# Phase_4.net
KiCad netlist of a schematic drawn in Altium Designer
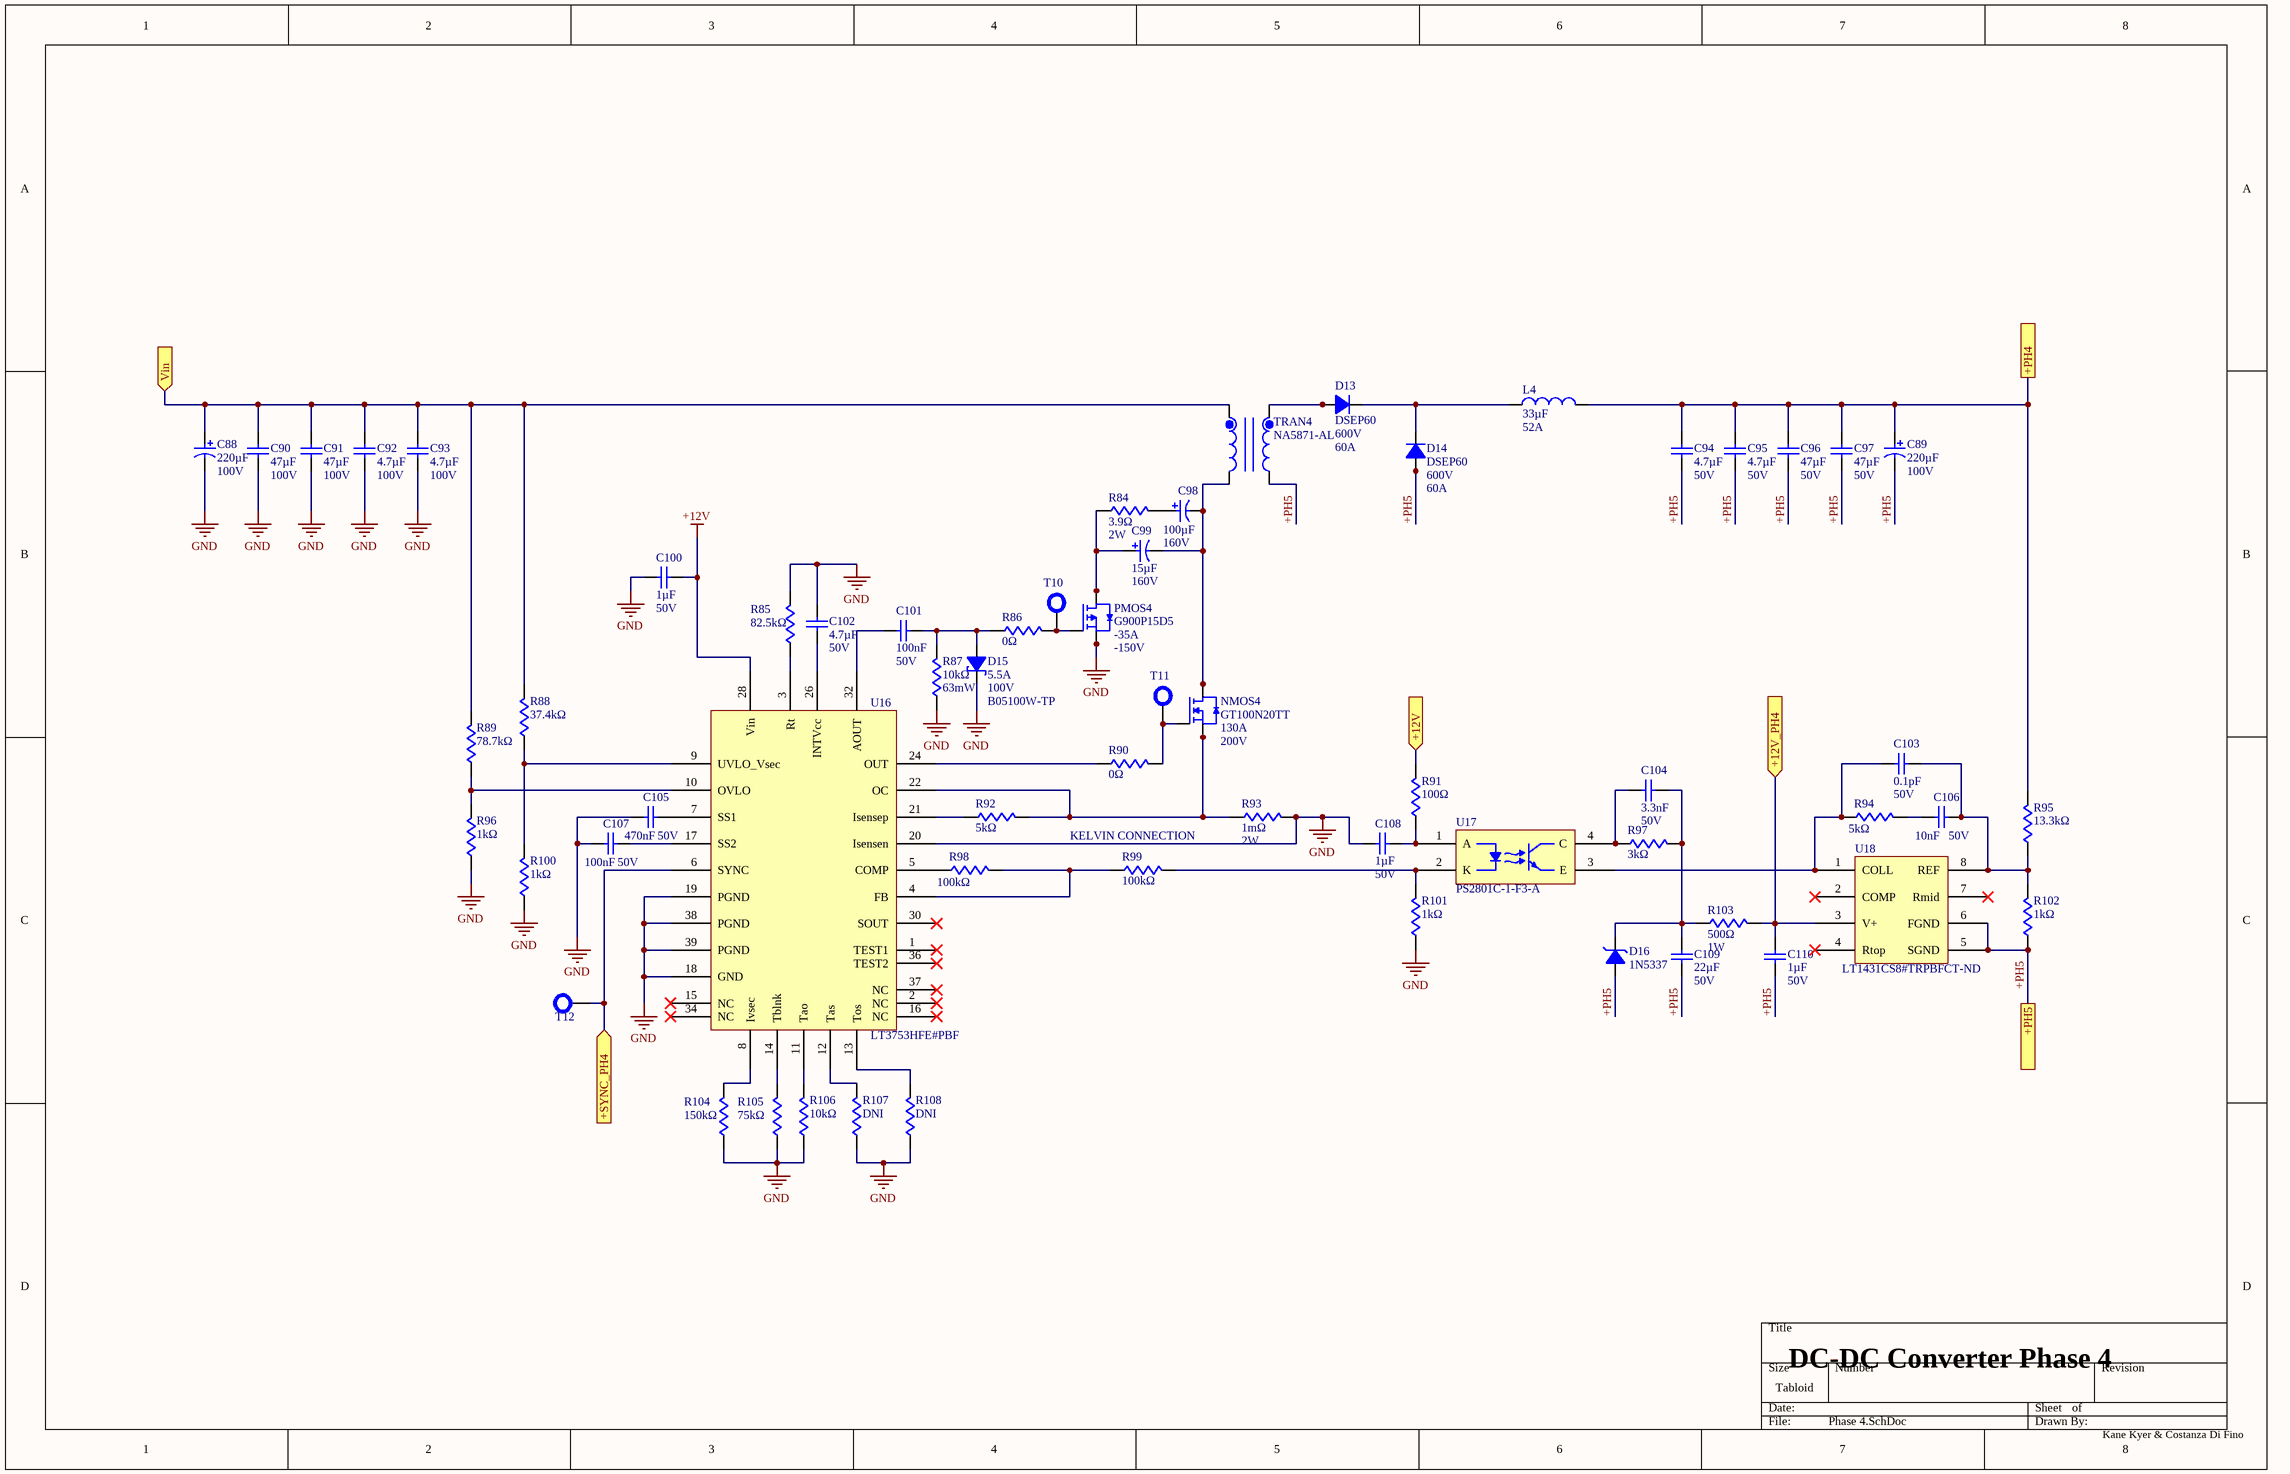
[diagram p0: Phase 4.SchDoc]

(export (version "E")
  (design (tool "Eeschema 10.0.6"))
  (components
    (comp (ref "C88")
      (value "220µF")
      (footprint "C_AEC")
      (description "Radial Can - SMD ALUMINUM ELECTROLYTIC CAPACITOR AFK 100V 220muF ±20% 0.709Dia 18.00mm")
      (fields
        (field (name "MANUFACTURER") "Cornell Dubilier")
        (field (name "MANUFACTURER PART NUMBER") "AFK227M2AR44T-F")
        (field (name "VOLTAGE RATING") "100V")
      )
      (libsource (lib "library") (part "AFK227M2AR44T-F"))
    )
    (comp (ref "C89")
      (value "220µF")
      (footprint "C_AEC")
      (description "Radial Can - SMD ALUMINUM ELECTROLYTIC CAPACITOR AFK 100V 220muF ±20% 0.709Dia 18.00mm")
      (fields
        (field (name "MANUFACTURER") "Cornell Dubilier")
        (field (name "MANUFACTURER PART NUMBER") "AFK227M2AR44T-F")
        (field (name "VOLTAGE RATING") "100V")
      )
      (libsource (lib "library") (part "AFK227M2AR44T-F"))
    )
    (comp (ref "C90")
      (value "47µF")
      (footprint "C_CAA573")
      (description "Multilayer Ceramic Chip Capacitors, Capacitance=47μF, LxWxT: 6.0x7.5x6.4mm")
      (fields
        (field (name "MANUFACTURER") "TDK")
        (field (name "MANUFACTURER PART NUMBER") "CAA573X7S2A476M640LH")
        (field (name "VOLTAGE RATING") "100V")
      )
      (libsource (lib "library") (part "CAA573X7S2A476M640LH"))
    )
    (comp (ref "C91")
      (value "47µF")
      (footprint "C_CAA573")
      (description "Multilayer Ceramic Chip Capacitors, Capacitance=47μF, LxWxT: 6.0x7.5x6.4mm")
      (fields
        (field (name "MANUFACTURER") "TDK")
        (field (name "MANUFACTURER PART NUMBER") "CAA573X7S2A476M640LH")
        (field (name "VOLTAGE RATING") "100V")
      )
      (libsource (lib "library") (part "CAA573X7S2A476M640LH"))
    )
    (comp (ref "C92")
      (value "4.7µF")
      (footprint "C_1210")
      (fields
        (field (name "MANUFACTURER") "Cal-Chip Electronics")
        (field (name "MANUFACTURER PART NUMBER") "GMC32X7S475K100NT")
        (field (name "VOLTAGE RATING (DC)") "100V")
      )
      (libsource (lib "library") (part "GMC32X7S475K100NT"))
    )
    (comp (ref "C93")
      (value "4.7µF")
      (footprint "C_1210")
      (fields
        (field (name "MANUFACTURER") "Cal-Chip Electronics")
        (field (name "MANUFACTURER PART NUMBER") "GMC32X7S475K100NT")
        (field (name "VOLTAGE RATING (DC)") "100V")
      )
      (libsource (lib "library") (part "GMC32X7S475K100NT"))
    )
    (comp (ref "C94")
      (value "4.7µF")
      (footprint "C_1206")
      (fields
        (field (name "MANUFACTURER") "Cal-Chip Electronics")
        (field (name "MANUFACTURER PART NUMBER") "GMC31X7R475K50NT")
        (field (name "VOLTAGE RATING (DC)") "50V")
      )
      (libsource (lib "library") (part "GMC31X7R475K50NT"))
    )
    (comp (ref "C95")
      (value "4.7µF")
      (footprint "C_1206")
      (fields
        (field (name "MANUFACTURER") "Cal-Chip Electronics")
        (field (name "MANUFACTURER PART NUMBER") "GMC31X7R475K50NT")
        (field (name "VOLTAGE RATING (DC)") "50V")
      )
      (libsource (lib "library") (part "GMC31X7R475K50NT"))
    )
    (comp (ref "C96")
      (value "47µF")
      (footprint "C_CKG57N")
      (fields
        (field (name "MANUFACTURER") "TDK")
        (field (name "MANUFACTURER PART NUMBER") "CKG57NX7R1H476M500JJ")
        (field (name "VOLTAGE RATING (DC)") "50V")
      )
      (libsource (lib "library") (part "CKG57NX7R1H476M500JJ"))
    )
    (comp (ref "C97")
      (value "47µF")
      (footprint "C_CKG57N")
      (fields
        (field (name "MANUFACTURER") "TDK")
        (field (name "MANUFACTURER PART NUMBER") "CKG57NX7R1H476M500JJ")
        (field (name "VOLTAGE RATING (DC)") "50V")
      )
      (libsource (lib "library") (part "CKG57NX7R1H476M500JJ"))
    )
    (comp (ref "C98")
      (value "100µF")
      (footprint "UUJ2C101MNJ1MS")
      (description "Aluminum Electrolytic Capacitors 100 F 160 V Radial, SMD 5000 Hrs 105C")
      (fields
        (field (name "MANUFACTURER") "Nichicon")
        (field (name "MANUFACTURER PART NUMBER") "UUJ2C101MNJ1MS")
        (field (name "VOLTAGE RATING (DC)") "160V")
      )
      (libsource (lib "library") (part "UUJ2C101MNJ1MS"))
    )
    (comp (ref "C99")
      (value "15µF")
      (footprint "ULT2C150MNL1GS")
      (description "Radial Can - SMD ALUMINUM ELECTROLYTIC CAPACITOR ULT 160V 15muF ±20% 0.315Dia 8.00mm")
      (fields
        (field (name "MANUFACTURER") "Nichicon")
        (field (name "MANUFACTURER PART NUMBER") "ULT2C150MNL1GS")
        (field (name "VOLTAGE") "160V")
      )
      (libsource (lib "library") (part "ULT2C150MNL1GS"))
    )
    (comp (ref "C100")
      (value "1µF")
      (footprint "C_0805")
      (description "50V 1uF X7R ±10% 0805 Multilayer Ceramic Capacitors MLCC - SMD/SMT ROHS")
      (fields
        (field (name "MANUFACTURER") "Samsung Electro-Mechanics")
        (field (name "MANUFACTURER PART NUMBER") "CL21B105KBFNNNE")
        (field (name "VOLTAGE") "50V")
      )
      (libsource (lib "library") (part "CL21B105KBFNNNE"))
    )
    (comp (ref "C101")
      (value "100nF")
      (footprint "C_0603")
      (description "50V 100nF X7R ±10% 0603 Multilayer Ceramic Capacitors MLCC - SMD/SMT ROHS")
      (fields
        (field (name "MANUFACTURER") "KEMET")
        (field (name "MANUFACTURER PART NUMBER") "C0603C104K5RACTU")
        (field (name "VOLTAGE RATING") "50V")
      )
      (libsource (lib "library") (part "C0603C104K5RACTU"))
    )
    (comp (ref "C102")
      (value "4.7µF")
      (footprint "C_1206")
      (fields
        (field (name "MANUFACTURER") "Cal-Chip Electronics")
        (field (name "MANUFACTURER PART NUMBER") "GMC31X7R475K50NT")
        (field (name "VOLTAGE RATING (DC)") "50V")
      )
      (libsource (lib "library") (part "GMC31X7R475K50NT"))
    )
    (comp (ref "C103")
      (value "0.1pF")
      (footprint "C_0402")
      (description "Multilayer Ceramic Capacitor, 0.1 pF, 50 V, ± 0.05pF, C0G (NP0), 0402 [1005 Metric]")
      (fields
        (field (name "MANUFACTURER") "Murata")
        (field (name "MANUFACTURER PART NUMBER") "GJM1555C1HR10WB01D")
        (field (name "VOLTAGE RATING") "50V")
      )
      (libsource (lib "library") (part "GJM1555C1HR10WB01D"))
    )
    (comp (ref "C104")
      (value "3.3nF")
      (footprint "C_0603")
      (description "50V 3.3nF C0G ±1% 0603 Multilayer Ceramic Capacitors MLCC - SMD/SMT ROHS")
      (fields
        (field (name "MANUFACTURER") "Murata")
        (field (name "MANUFACTURER PART NUMBER") "GCM1885C1H332FA16D")
        (field (name "VOLTAGE RATING") "50V")
      )
      (libsource (lib "library") (part "GCM1885C1H332FA16D"))
    )
    (comp (ref "C105")
      (value "470nF")
      (footprint "C_0402")
      (description "50V 470nF X5R ±10% 0402 Multilayer Ceramic Capacitors MLCC - SMD/SMT ROHS")
      (fields
        (field (name "MANUFACTURER") "Murata")
        (field (name "MANUFACTURER PART NUMBER") "GRM155R61H474KE11D")
        (field (name "VOLTAGE RATING") "50V")
      )
      (libsource (lib "library") (part "GRM155R61H474KE11D"))
    )
    (comp (ref "C106")
      (value "10nF")
      (footprint "C_0603")
      (description "Capacitor, Multilayer, Ceramic, 50V, 10%, X7R, 15% Tc, 0.01Uf, Surface Mount, 0603")
      (fields
        (field (name "MANUFACTURER") "KEMET")
        (field (name "MANUFACTURER PART NUMBER") "C0603C103K5RACTU")
        (field (name "VOLTAGE RATING") "50V")
      )
      (libsource (lib "library") (part "C0603C103K5RACTU"))
    )
    (comp (ref "C107")
      (value "100nF")
      (footprint "C_0603")
      (description "50V 100nF X7R ±10% 0603 Multilayer Ceramic Capacitors MLCC - SMD/SMT ROHS")
      (fields
        (field (name "MANUFACTURER") "KEMET")
        (field (name "MANUFACTURER PART NUMBER") "C0603C104K5RACTU")
        (field (name "VOLTAGE RATING") "50V")
      )
      (libsource (lib "library") (part "C0603C104K5RACTU"))
    )
    (comp (ref "C108")
      (value "1µF")
      (footprint "C_0805")
      (description "50V 1uF X7R ±10% 0805 Multilayer Ceramic Capacitors MLCC - SMD/SMT ROHS")
      (fields
        (field (name "MANUFACTURER") "Samsung Electro-Mechanics")
        (field (name "MANUFACTURER PART NUMBER") "CL21B105KBFNNNE")
        (field (name "VOLTAGE") "50V")
      )
      (libsource (lib "library") (part "CL21B105KBFNNNE"))
    )
    (comp (ref "C109")
      (value "22µF")
      (footprint "C_2220")
      (fields
        (field (name "MANUFACTURER") "Cal-Chip Electronics")
        (field (name "MANUFACTURER PART NUMBER") "GMC55X7R226M50NT")
        (field (name "VOLTAGE RATING (DC)") "50V")
      )
      (libsource (lib "library") (part "GMC55X7R226M50NT"))
    )
    (comp (ref "C110")
      (value "1µF")
      (footprint "C_0805")
      (description "50V 1uF X7R ±10% 0805 Multilayer Ceramic Capacitors MLCC - SMD/SMT ROHS")
      (fields
        (field (name "MANUFACTURER") "Samsung Electro-Mechanics")
        (field (name "MANUFACTURER PART NUMBER") "CL21B105KBFNNNE")
        (field (name "VOLTAGE") "50V")
      )
      (libsource (lib "library") (part "CL21B105KBFNNNE"))
    )
    (comp (ref "D13")
      (value "DSEP60")
      (footprint "D_DSEP60")
      (description "Power Diode Discretes-FRED TO-")
      (fields
        (field (name "MANUFACTURER") "IXYS")
        (field (name "MANUFACTURER PART NUMBER") "DSEP60-06AZ-TRL")
        (field (name "VR") "600V")
        (field (name "IO") "60A")
      )
      (libsource (lib "library") (part "DSEP60-06AZ-TRL"))
    )
    (comp (ref "D14")
      (value "DSEP60")
      (footprint "D_DSEP60")
      (description "Power Diode Discretes-FRED TO-")
      (fields
        (field (name "MANUFACTURER") "IXYS")
        (field (name "MANUFACTURER PART NUMBER") "DSEP60-06AZ-TRL")
        (field (name "VR") "600V")
        (field (name "IO") "60A")
      )
      (libsource (lib "library") (part "DSEP60-06AZ-TRL"))
    )
    (comp (ref "D15")
      (value "B05100W-TP")
      (footprint "D_B05100W")
      (description "Rectifier Diode, Schottky, 1 Phase, 1 Element, 0.5A, 100V V(RRM), Silicon")
      (fields
        (field (name "MANUFACTURER") "MCC")
        (field (name "MAX FORWARD SURGE CURRENT (IFSM)") "5.5A")
        (field (name "MIN BREAKDOWN VOLTAGE") "100V")
        (field (name "MANUFACTURER PART NUMBER") "B05100W-TP")
      )
      (libsource (lib "library") (part "B05100W-TP"))
    )
    (comp (ref "D16")
      (value "1N5337BRLG")
      (footprint "D_1N5337")
      (description "Zener Diode Single 4.7V 5% 2Ohm 5000mW 2-Pin Case 017AA-01 T/R / DIODE ZENER 4.7V 5W AXIAL")
      (fields
        (field (name "MANUFACTURER") "onsemi")
        (field (name "TOLERANCE") "5%")
        (field (name "SUPPLIER PART NUMBER") "1N5337")
      )
      (libsource (lib "library") (part "1N5337BRLG"))
    )
    (comp (ref "L4")
      (value "33µF")
      (footprint "CPEX4141L-330MC")
      (description "Fixed Ind 33UH 52A 1.88 Mohm Th")
      (fields
        (field (name "MANUFACTURER") "Codaca")
        (field (name "MANUFACTURER PART NUMBER") "CPEX4141L-330MC")
        (field (name "IRMS") "52A")
      )
      (libsource (lib "library") (part "CPEX4141L-330MC"))
    )
    (comp (ref "NMOS4")
      (value "GT100N20TT")
      (footprint "GT100N20TT")
      (description "Mosfet N-ch 200V 130A 280W Tolt")
      (fields
        (field (name "MANUFACTURER") "GoFord")
        (field (name "MANUFACTURER PART NUMBER") "GT100N20TT")
        (field (name "ID") "130A")
        (field (name "VDS") "200V")
      )
      (libsource (lib "library") (part "GT100N20TT"))
    )
    (comp (ref "PMOS4")
      (value "G900P15D5")
      (footprint "G900P15")
      (description "P-150V, -60A, RD(max) Less Than 80mOhm at -10V, VTH -1V to -4V, DFN5x6-8L")
      (fields
        (field (name "MANUFACTURER") "GoFord")
        (field (name "MANUFACTURER PART NUMBER") "G900P15D5")
        (field (name "ID") "-35A")
        (field (name "VDS") "-150V")
      )
      (libsource (lib "library") (part "G900P15D5"))
    )
    (comp (ref "R84")
      (value "3.9Ω")
      (footprint "R_SM2W")
      (description "SM Series 3.9 Ohm ±5 % 2 W ±200 ppm/°C Surface Mount Wirewound Resistor")
      (fields
        (field (name "MANUFACTURER") "TE Connectivity")
        (field (name "MANUFACTURER PART NUMBER") "SMW23R9JT")
        (field (name "POWER RATING") "2W")
      )
      (libsource (lib "library") (part "SMW23R9JT"))
    )
    (comp (ref "R85")
      (value "82.5kΩ")
      (footprint "R_0805")
      (description "Res Thick Film 0805 82.5K Ohm 1% 1/8W ±100ppm/°C Molded SMD SMD Paper T/R")
      (fields
        (field (name "MANUFACTURER") "Stackpole Electronics")
        (field (name "MANUFACTURER PART NUMBER") "RMCF0805FT82K5")
      )
      (libsource (lib "library") (part "RMCF0805FT82K5"))
    )
    (comp (ref "R86")
      (value "0Ω")
      (footprint "R_0805")
      (description "Zero Ohm Resistor, Jumper, 0805 [2012 Metric], Thick Film, 125 mW, 2.5 A, Surface Mount Device")
      (fields
        (field (name "MANUFACTURER") "Vishay")
        (field (name "MANUFACTURER PART NUMBER") "CRCW08050000Z0EA")
      )
      (libsource (lib "library") (part "CRCW08050000Z0EA"))
    )
    (comp (ref "R87")
      (value "10kΩ")
      (footprint "R_0402")
      (description "Fixed Resistor, Metal Glaze/thick Film, 0.0625W, 10000ohm, 50V, 1% +/-Tol, Surface Mount, 0402")
      (fields
        (field (name "MANUFACTURER") "Cal-Chip Electronics")
        (field (name "MANUFACTURER PART NUMBER") "RM04F1002CT")
        (field (name "POWER RATING") "63mW")
      )
      (libsource (lib "library") (part "RM04F1002CT"))
    )
    (comp (ref "R88")
      (value "37.4kΩ")
      (footprint "R_0603")
      (description "100mW Thick Film Resistors 75V ±100ppm/℃ ±1% 37.4kΩ 0603 Chip Resistor - Surface Mount ROHS")
      (fields
        (field (name "MANUFACTURER") "Yageo Group")
        (field (name "MANUFACTURER PART NUMBER") "RC0603FR-0737K4L")
      )
      (libsource (lib "library") (part "RC0603FR-0737K4L"))
    )
    (comp (ref "R89")
      (value "78.7kΩ")
      (footprint "R_0603")
      (description "Res Thick Film 0603 78.7K Ohm 1% 0.1W(1/10W) ±100ppm/C Pad SMD T/R")
      (fields
        (field (name "MANUFACTURER") "Yageo Group")
        (field (name "MANUFACTURER PART NUMBER") "RC0603FR-0778K7L")
      )
      (libsource (lib "library") (part "RC0603FR-0778K7L"))
    )
    (comp (ref "R90")
      (value "0Ω")
      (footprint "R_0805")
      (description "Zero Ohm Resistor, Jumper, 0805 [2012 Metric], Thick Film, 125 mW, 2.5 A, Surface Mount Device")
      (fields
        (field (name "MANUFACTURER") "Vishay")
        (field (name "MANUFACTURER PART NUMBER") "CRCW08050000Z0EA")
      )
      (libsource (lib "library") (part "CRCW08050000Z0EA"))
    )
    (comp (ref "R91")
      (value "100Ω")
      (footprint "R_0603")
      (description "Yageo RC0603FR-07100RL 0603 SMD Resistor 100 Ohm thin film chip resistor")
      (fields
        (field (name "MANUFACTURER") "Yageo Group")
        (field (name "MANUFACTURER PART NUMBER") "RC0603FR-07100RL")
      )
      (libsource (lib "library") (part "RC0603FR-07100RL"))
    )
    (comp (ref "R92")
      (value "5kΩ")
      (footprint "R_0402")
      (description "Res Thin Film 0402 5K Ohm 0.1% 0.05W(1/20W) +/-25ppm/C Sulfur Resistant Pad SMD Medical T/R")
      (fields
        (field (name "MANUFACTURER") "Vishay")
        (field (name "MANUFACTURER PART NUMBER") "PNM0402E5001BST1")
      )
      (libsource (lib "library") (part "PNM0402E5001BST1"))
    )
    (comp (ref "R93")
      (value "1mΩ")
      (footprint "R_2512")
      (description "Res Thick Film 2512 1m Ohm 1% 2W ±75ppm/°C Molded SMD Embossed T/R")
      (fields
        (field (name "MANUFACTURER") "Bourns")
        (field (name "MANUFACTURER PART NUMBER") "CRE2512-FZ-R001E-2")
        (field (name "POWER RATING") "2W")
      )
      (libsource (lib "library") (part "CRE2512-FZ-R001E-2"))
    )
    (comp (ref "R94")
      (value "5kΩ")
      (footprint "R_0402")
      (description "Res Thin Film 0402 5K Ohm 0.1% 0.05W(1/20W) +/-25ppm/C Sulfur Resistant Pad SMD Medical T/R")
      (fields
        (field (name "MANUFACTURER") "Vishay")
        (field (name "MANUFACTURER PART NUMBER") "PNM0402E5001BST1")
      )
      (libsource (lib "library") (part "PNM0402E5001BST1"))
    )
    (comp (ref "R95")
      (value "13.3kΩ")
      (footprint "R_0603")
      (description "Res Thick Film 0603 13.3K Ohm 1% 0.1W(1/10W) ±100ppm/C Pad SMD Automotive T/R")
      (fields
        (field (name "MANUFACTURER") "Stackpole Electronics")
        (field (name "MANUFACTURER PART NUMBER") "RMCF0603FT13K3")
      )
      (libsource (lib "library") (part "RMCF0603FT13K3"))
    )
    (comp (ref "R96")
      (value "1kΩ")
      (footprint "R_0402")
      (description "62.5mW Thick Film Resistors ±100ppm/℃ ±1% 1kΩ 0402 Chip Resistor - Surface Mount ROHS")
      (fields
        (field (name "MANUFACTURER") "Cal-Chip Electronics")
        (field (name "MANUFACTURER PART NUMBER") "RM04F1001CT")
      )
      (libsource (lib "library") (part "RM04F1001CT"))
    )
    (comp (ref "R97")
      (value "3kΩ")
      (footprint "C_0402")
      (description "Res Thick Film 0402 3K Ohm 1% 0.063W(1/16W) ±100ppm/C Pad SMD Automotive T/R")
      (fields
        (field (name "MANUFACTURER") "Yageo Group")
        (field (name "MANUFACTURER PART NUMBER") "AC0402FR-073KL")
      )
      (libsource (lib "library") (part "AC0402FR-073KL"))
    )
    (comp (ref "R98")
      (value "100kΩ")
      (footprint "R_0402")
      (description "Fixed Resistor, Metal Glaze/thick Film, 0.0625W, 100000ohm, 50V, 1% +/-Tol, Surface Mount, 0402")
      (fields
        (field (name "MANUFACTURER") "Cal-Chip Electronics")
        (field (name "MANUFACTURER PART NUMBER") "RM04F1003CT")
      )
      (libsource (lib "library") (part "RM04F1003CT"))
    )
    (comp (ref "R99")
      (value "100kΩ")
      (footprint "R_0402")
      (description "Fixed Resistor, Metal Glaze/thick Film, 0.0625W, 100000ohm, 50V, 1% +/-Tol, Surface Mount, 0402")
      (fields
        (field (name "MANUFACTURER") "Cal-Chip Electronics")
        (field (name "MANUFACTURER PART NUMBER") "RM04F1003CT")
      )
      (libsource (lib "library") (part "RM04F1003CT"))
    )
    (comp (ref "R100")
      (value "1kΩ")
      (footprint "R_0402")
      (description "62.5mW Thick Film Resistors ±100ppm/℃ ±1% 1kΩ 0402 Chip Resistor - Surface Mount ROHS")
      (fields
        (field (name "MANUFACTURER") "Cal-Chip Electronics")
        (field (name "MANUFACTURER PART NUMBER") "RM04F1001CT")
      )
      (libsource (lib "library") (part "RM04F1001CT"))
    )
    (comp (ref "R101")
      (value "1kΩ")
      (footprint "R_0402")
      (description "62.5mW Thick Film Resistors ±100ppm/℃ ±1% 1kΩ 0402 Chip Resistor - Surface Mount ROHS")
      (fields
        (field (name "MANUFACTURER") "Cal-Chip Electronics")
        (field (name "MANUFACTURER PART NUMBER") "RM04F1001CT")
      )
      (libsource (lib "library") (part "RM04F1001CT"))
    )
    (comp (ref "R102")
      (value "1kΩ")
      (footprint "R_0402")
      (description "62.5mW Thick Film Resistors ±100ppm/℃ ±1% 1kΩ 0402 Chip Resistor - Surface Mount ROHS")
      (fields
        (field (name "MANUFACTURER") "Cal-Chip Electronics")
        (field (name "MANUFACTURER PART NUMBER") "RM04F1001CT")
      )
      (libsource (lib "library") (part "RM04F1001CT"))
    )
    (comp (ref "R103")
      (value "500Ω")
      (footprint "R_WSC2515")
      (description "Fixed Resistor, Wire Wound, 1W, 500ohm, 22.3607V, 1% +/-Tol, 20ppm/Cel, Surface Mount, 2515")
      (fields
        (field (name "MANUFACTURER") "Vishay")
        (field (name "MANUFACTURER PART NUMBER") "WSC2515500R0FEB")
        (field (name "POWER RATING") "1W")
      )
      (libsource (lib "library") (part "WSC2515500R0FEB"))
    )
    (comp (ref "R104")
      (value "150kΩ")
      (footprint "R_0603")
      (description "100mW Thick Film Resistors 75V ±100ppm/℃ ±1% 150kΩ 0603 Chip Resistor - Surface Mount ROHS")
      (fields
        (field (name "MANUFACTURER") "Yageo Group")
        (field (name "MANUFACTURER PART NUMBER") "RC0603FR-07150KL")
      )
      (libsource (lib "library") (part "RC0603FR-07150KL"))
    )
    (comp (ref "R105")
      (value "75kΩ")
      (footprint "R_0603")
      (description "Res Thick Film 0603 75K Ohm 1% 0.1W(1/10W) ±100ppm/C Pad SMD T/R Automotive AEC-Q200")
      (fields
        (field (name "MANUFACTURER") "Yageo Group")
        (field (name "MANUFACTURER PART NUMBER") "AC0603FR-0775KL")
      )
      (libsource (lib "library") (part "AC0603FR-0775KL"))
    )
    (comp (ref "R106")
      (value "10kΩ")
      (footprint "R_0402")
      (description "Fixed Resistor, Metal Glaze/thick Film, 0.0625W, 10000ohm, 50V, 1% +/-Tol, Surface Mount, 0402")
      (fields
        (field (name "MANUFACTURER") "Cal-Chip Electronics")
        (field (name "MANUFACTURER PART NUMBER") "RM04F1002CT")
      )
      (libsource (lib "library") (part "RM04F1002CT"))
    )
    (comp (ref "R107")
      (value "DNI")
      (footprint "R_0805")
      (description "Zero Ohm Resistor, Jumper, 0805 [2012 Metric], Thick Film, 125 mW, 2.5 A, Surface Mount Device")
      (fields
        (field (name "MANUFACTURER") "Vishay")
        (field (name "MANUFACTURER PART NUMBER") "CRCW08050000Z0EA")
      )
      (libsource (lib "library") (part "CRCW08050000Z0EA"))
    )
    (comp (ref "R108")
      (value "DNI")
      (footprint "R_0805")
      (description "Zero Ohm Resistor, Jumper, 0805 [2012 Metric], Thick Film, 125 mW, 2.5 A, Surface Mount Device")
      (fields
        (field (name "MANUFACTURER") "Vishay")
        (field (name "MANUFACTURER PART NUMBER") "CRCW08050000Z0EA")
      )
      (libsource (lib "library") (part "CRCW08050000Z0EA"))
    )
    (comp (ref "T10") (value "TEST") (footprint "TEST_POINT") (libsource (lib "library") (part "TEST")))
    (comp (ref "T11") (value "TEST") (footprint "TEST_POINT") (libsource (lib "library") (part "TEST")))
    (comp (ref "T12") (value "TEST") (footprint "TEST_POINT") (libsource (lib "library") (part "TEST")))
    (comp (ref "TRAN4")
      (value "NA5871-AL")
      (footprint "NA5871-AL")
      (description "Transformer, planar, for TI UCC28950, SMT, RoHS")
      (fields (field (name "MANUFACTURER") "Coilcraft") (field (name "SUPPLIER PART NUMBER") "NA5871-AL"))
      (libsource (lib "library") (part "NA5871-AL"))
    )
    (comp (ref "U16")
      (value "LT3753HFE#PBF")
      (footprint "LT3753")
      (description "500kHz 8.5V~100V Buck-boost type 1 TSSOP-38-EP-4.4mm DC-DC Controllers ROHS")
      (fields
        (field (name "MANUFACTURER") "Analog Devices")
        (field (name "MANUFACTURER PART NUMBER") "LT3753HFE#PBF")
      )
      (libsource (lib "library") (part "LT3753HFE#PBF"))
    )
    (comp (ref "U17")
      (value "PS2801C-1-F3-A")
      (footprint "PS2801C")
      (description "Optocoupler DC-IN 1-CH Transistor DC-OUT 4-Pin SSOP T/R")
      (fields
        (field (name "MANUFACTURER") "Renesas")
        (field (name "MANUFACTURER PART NUMBER") "PS2801C-1-F3-A")
      )
      (libsource (lib "library") (part "PS2801C-1-F3-A"))
    )
    (comp (ref "U18")
      (value "LT1431CS8#TRPBF")
      (footprint "LT1431")
      (description "V-Ref Adjustable 2.5V to 36V 100mA 8-Pin SOIC N T/R")
      (fields
        (field (name "SUPPLIER PART NUMBER") "LT1431CS8#TRPBFCT-ND")
        (field (name "MANUFACTURER") "Analog Devices")
        (field (name "TOLERANCE") "0.4%")
      )
      (libsource (lib "library") (part "LT1431CS8#TRPBF"))
    )
  )
  (nets
    (net (code "1") (name "+12V") (class "Default")
      (node (ref "C100") (pin "2") (pintype "passive"))
      (node (ref "R91") (pin "2") (pintype "passive"))
      (node (ref "U16") (pin "28") (pinfunction "Vin_28") (pintype "passive"))
    )
    (net (code "2") (name "/+12V_PH4") (class "Default")
      (node (ref "C110") (pin "2") (pintype "passive"))
      (node (ref "R103") (pin "2") (pintype "passive"))
      (node (ref "U18") (pin "3") (pinfunction "V+_3") (pintype "passive"))
    )
    (net (code "3") (name "/+PH4") (class "Default")
      (node (ref "C89") (pin "1") (pintype "passive"))
      (node (ref "C94") (pin "2") (pintype "passive"))
      (node (ref "C95") (pin "2") (pintype "passive"))
      (node (ref "C96") (pin "2") (pintype "passive"))
      (node (ref "C97") (pin "2") (pintype "passive"))
      (node (ref "L4") (pin "2") (pintype "passive"))
      (node (ref "R95") (pin "2") (pintype "passive"))
    )
    (net (code "4") (name "/+PH5") (class "Default")
      (node (ref "C109") (pin "1") (pintype "passive"))
      (node (ref "C110") (pin "1") (pintype "passive"))
      (node (ref "C89") (pin "2") (pintype "passive"))
      (node (ref "C94") (pin "1") (pintype "passive"))
      (node (ref "C95") (pin "1") (pintype "passive"))
      (node (ref "C96") (pin "1") (pintype "passive"))
      (node (ref "C97") (pin "1") (pintype "passive"))
      (node (ref "D14") (pin "1") (pinfunction "A_1") (pintype "passive"))
      (node (ref "D14") (pin "3") (pinfunction "A_3") (pintype "passive"))
      (node (ref "D16") (pin "2") (pintype "passive"))
      (node (ref "R102") (pin "1") (pintype "passive"))
      (node (ref "TRAN4") (pin "11") (pintype "passive"))
      (node (ref "U18") (pin "5") (pinfunction "SGND_5") (pintype "passive"))
      (node (ref "U18") (pin "6") (pinfunction "FGND_6") (pintype "passive"))
    )
    (net (code "5") (name "/+SYNC_PH4") (class "Default")
      (node (ref "T12") (pin "1") (pinfunction "1_1") (pintype "passive"))
      (node (ref "U16") (pin "6") (pinfunction "SYNC_6") (pintype "passive"))
    )
    (net (code "6") (name "/Vin") (class "Default")
      (node (ref "C88") (pin "1") (pintype "passive"))
      (node (ref "C90") (pin "2") (pintype "passive"))
      (node (ref "C91") (pin "2") (pintype "passive"))
      (node (ref "C92") (pin "2") (pintype "passive"))
      (node (ref "C93") (pin "2") (pintype "passive"))
      (node (ref "R88") (pin "2") (pintype "passive"))
      (node (ref "R89") (pin "2") (pintype "passive"))
      (node (ref "TRAN4") (pin "1") (pintype "passive"))
    )
    (net (code "7") (name "GND") (class "Default")
      (node (ref "C100") (pin "1") (pintype "passive"))
      (node (ref "C102") (pin "1") (pintype "passive"))
      (node (ref "C105") (pin "1") (pintype "passive"))
      (node (ref "C107") (pin "1") (pintype "passive"))
      (node (ref "C108") (pin "1") (pintype "passive"))
      (node (ref "C88") (pin "2") (pintype "passive"))
      (node (ref "C90") (pin "1") (pintype "passive"))
      (node (ref "C91") (pin "1") (pintype "passive"))
      (node (ref "C92") (pin "1") (pintype "passive"))
      (node (ref "C93") (pin "1") (pintype "passive"))
      (node (ref "D15") (pin "1") (pintype "passive"))
      (node (ref "PMOS4") (pin "1") (pinfunction "S_1") (pintype "passive"))
      (node (ref "PMOS4") (pin "2") (pinfunction "S_2") (pintype "passive"))
      (node (ref "PMOS4") (pin "3") (pinfunction "S_3") (pintype "passive"))
      (node (ref "R100") (pin "1") (pintype "passive"))
      (node (ref "R101") (pin "1") (pintype "passive"))
      (node (ref "R104") (pin "1") (pintype "passive"))
      (node (ref "R105") (pin "1") (pintype "passive"))
      (node (ref "R106") (pin "1") (pintype "passive"))
      (node (ref "R107") (pin "1") (pintype "passive"))
      (node (ref "R108") (pin "1") (pintype "passive"))
      (node (ref "R85") (pin "2") (pintype "passive"))
      (node (ref "R87") (pin "1") (pintype "passive"))
      (node (ref "R93") (pin "2") (pintype "passive"))
      (node (ref "R96") (pin "1") (pintype "passive"))
      (node (ref "U16") (pin "18") (pinfunction "GND_18") (pintype "passive"))
      (node (ref "U16") (pin "19") (pinfunction "PGND_19") (pintype "passive"))
      (node (ref "U16") (pin "20") (pinfunction "Isensen_20") (pintype "passive"))
      (node (ref "U16") (pin "38") (pinfunction "PGND_38") (pintype "passive"))
      (node (ref "U16") (pin "39") (pinfunction "PGND_39") (pintype "passive"))
    )
    (net (code "8") (name "Net-(C98-Pad1)") (class "Default")
      (node (ref "C98") (pin "1") (pintype "passive"))
      (node (ref "R84") (pin "2") (pintype "passive"))
    )
    (net (code "9") (name "Net-(C98-Pad2)") (class "Default")
      (node (ref "C98") (pin "2") (pintype "passive"))
      (node (ref "C99") (pin "2") (pintype "passive"))
      (node (ref "NMOS4") (pin "10") (pinfunction "D_10") (pintype "passive"))
      (node (ref "NMOS4") (pin "11") (pinfunction "D_11") (pintype "passive"))
      (node (ref "NMOS4") (pin "12") (pinfunction "D_12") (pintype "passive"))
      (node (ref "NMOS4") (pin "13") (pinfunction "D_13") (pintype "passive"))
      (node (ref "NMOS4") (pin "14") (pinfunction "D_14") (pintype "passive"))
      (node (ref "NMOS4") (pin "15") (pinfunction "D_15") (pintype "passive"))
      (node (ref "NMOS4") (pin "16") (pinfunction "D_16") (pintype "passive"))
      (node (ref "NMOS4") (pin "9") (pinfunction "D_9") (pintype "passive"))
      (node (ref "TRAN4") (pin "4") (pintype "passive"))
    )
    (net (code "10") (name "Net-(C99-Pad1)") (class "Default")
      (node (ref "C99") (pin "1") (pintype "passive"))
      (node (ref "PMOS4") (pin "5") (pinfunction "D_5") (pintype "passive"))
      (node (ref "PMOS4") (pin "6") (pinfunction "D_6") (pintype "passive"))
      (node (ref "PMOS4") (pin "7") (pinfunction "D_7") (pintype "passive"))
      (node (ref "PMOS4") (pin "8") (pinfunction "D_8") (pintype "passive"))
      (node (ref "R84") (pin "1") (pintype "passive"))
    )
    (net (code "11") (name "Net-(C101-Pad2)") (class "Default")
      (node (ref "C101") (pin "2") (pintype "passive"))
      (node (ref "D15") (pin "2") (pintype "passive"))
      (node (ref "R86") (pin "1") (pintype "passive"))
      (node (ref "R87") (pin "2") (pintype "passive"))
    )
    (net (code "12") (name "Net-(C104-Pad2)") (class "Default")
      (node (ref "C104") (pin "2") (pintype "passive"))
      (node (ref "C109") (pin "2") (pintype "passive"))
      (node (ref "D16") (pin "1") (pintype "passive"))
      (node (ref "R103") (pin "1") (pintype "passive"))
      (node (ref "R97") (pin "2") (pintype "passive"))
    )
    (net (code "13") (name "Net-(C106-Pad1)") (class "Default")
      (node (ref "C106") (pin "1") (pintype "passive"))
      (node (ref "R94") (pin "2") (pintype "passive"))
    )
    (net (code "14") (name "Net-(D13-A-Pad1)") (class "Default")
      (node (ref "D13") (pin "1") (pinfunction "A_1") (pintype "passive"))
      (node (ref "D13") (pin "3") (pinfunction "A_3") (pintype "passive"))
      (node (ref "TRAN4") (pin "6") (pintype "passive"))
    )
    (net (code "15") (name "Net-(D13-C)") (class "Default")
      (node (ref "D13") (pin "4") (pinfunction "C_4") (pintype "passive"))
      (node (ref "D14") (pin "4") (pinfunction "C_4") (pintype "passive"))
      (node (ref "L4") (pin "1") (pintype "passive"))
    )
    (net (code "16") (name "Net-(NMOS4-G)") (class "Default")
      (node (ref "NMOS4") (pin "8") (pinfunction "G_8") (pintype "passive"))
      (node (ref "R90") (pin "2") (pintype "passive"))
      (node (ref "T11") (pin "1") (pinfunction "1_1") (pintype "passive"))
    )
    (net (code "17") (name "Net-(PMOS4-G)") (class "Default")
      (node (ref "PMOS4") (pin "4") (pinfunction "G_4") (pintype "passive"))
      (node (ref "R86") (pin "2") (pintype "passive"))
      (node (ref "T10") (pin "1") (pinfunction "1_1") (pintype "passive"))
    )
    (net (code "18") (name "Net-(U16-AOUT)") (class "Default")
      (node (ref "C101") (pin "1") (pintype "passive"))
      (node (ref "U16") (pin "32") (pinfunction "AOUT_32") (pintype "passive"))
    )
    (net (code "19") (name "Net-(U16-COMP)") (class "Default")
      (node (ref "R98") (pin "1") (pintype "passive"))
      (node (ref "U16") (pin "5") (pinfunction "COMP_5") (pintype "passive"))
    )
    (net (code "20") (name "Net-(U16-FB)") (class "Default")
      (node (ref "R98") (pin "2") (pintype "passive"))
      (node (ref "R99") (pin "1") (pintype "passive"))
      (node (ref "U16") (pin "4") (pinfunction "FB_4") (pintype "passive"))
    )
    (net (code "21") (name "Net-(U16-INTVcc)") (class "Default")
      (node (ref "C102") (pin "2") (pintype "passive"))
      (node (ref "U16") (pin "26") (pinfunction "INTVcc_26") (pintype "passive"))
    )
    (net (code "22") (name "Net-(U16-Isensep)") (class "Default")
      (node (ref "R92") (pin "1") (pintype "passive"))
      (node (ref "U16") (pin "21") (pinfunction "Isensep_21") (pintype "passive"))
    )
    (net (code "23") (name "Net-(U16-Ivsec)") (class "Default")
      (node (ref "R104") (pin "2") (pintype "passive"))
      (node (ref "U16") (pin "8") (pinfunction "Ivsec_8") (pintype "passive"))
    )
    (net (code "24") (name "Net-(U16-OC)") (class "Default")
      (node (ref "NMOS4") (pin "1") (pinfunction "S_1") (pintype "passive"))
      (node (ref "NMOS4") (pin "2") (pinfunction "S_2") (pintype "passive"))
      (node (ref "NMOS4") (pin "3") (pinfunction "S_3") (pintype "passive"))
      (node (ref "NMOS4") (pin "4") (pinfunction "S_4") (pintype "passive"))
      (node (ref "NMOS4") (pin "5") (pinfunction "S_5") (pintype "passive"))
      (node (ref "NMOS4") (pin "6") (pinfunction "S_6") (pintype "passive"))
      (node (ref "NMOS4") (pin "7") (pinfunction "S_7") (pintype "passive"))
      (node (ref "R92") (pin "2") (pintype "passive"))
      (node (ref "R93") (pin "1") (pintype "passive"))
      (node (ref "U16") (pin "22") (pinfunction "OC_22") (pintype "passive"))
    )
    (net (code "25") (name "Net-(U16-OUT)") (class "Default")
      (node (ref "R90") (pin "1") (pintype "passive"))
      (node (ref "U16") (pin "24") (pinfunction "OUT_24") (pintype "passive"))
    )
    (net (code "26") (name "Net-(U16-OVLO)") (class "Default")
      (node (ref "R89") (pin "1") (pintype "passive"))
      (node (ref "R96") (pin "2") (pintype "passive"))
      (node (ref "U16") (pin "10") (pinfunction "OVLO_10") (pintype "passive"))
    )
    (net (code "27") (name "Net-(U16-Rt)") (class "Default")
      (node (ref "R85") (pin "1") (pintype "passive"))
      (node (ref "U16") (pin "3") (pinfunction "Rt_3") (pintype "passive"))
    )
    (net (code "28") (name "Net-(U16-SS1)") (class "Default")
      (node (ref "C105") (pin "2") (pintype "passive"))
      (node (ref "U16") (pin "7") (pinfunction "SS1_7") (pintype "passive"))
    )
    (net (code "29") (name "Net-(U16-SS2)") (class "Default")
      (node (ref "C107") (pin "2") (pintype "passive"))
      (node (ref "U16") (pin "17") (pinfunction "SS2_17") (pintype "passive"))
    )
    (net (code "30") (name "Net-(U16-Tao)") (class "Default")
      (node (ref "R106") (pin "2") (pintype "passive"))
      (node (ref "U16") (pin "11") (pinfunction "Tao_11") (pintype "passive"))
    )
    (net (code "31") (name "Net-(U16-Tas)") (class "Default")
      (node (ref "R107") (pin "2") (pintype "passive"))
      (node (ref "U16") (pin "12") (pinfunction "Tas_12") (pintype "passive"))
    )
    (net (code "32") (name "Net-(U16-Tblnk)") (class "Default")
      (node (ref "R105") (pin "2") (pintype "passive"))
      (node (ref "U16") (pin "14") (pinfunction "Tblnk_14") (pintype "passive"))
    )
    (net (code "33") (name "Net-(U16-Tos)") (class "Default")
      (node (ref "R108") (pin "2") (pintype "passive"))
      (node (ref "U16") (pin "13") (pinfunction "Tos_13") (pintype "passive"))
    )
    (net (code "34") (name "Net-(U16-UVLO_Vsec)") (class "Default")
      (node (ref "R100") (pin "2") (pintype "passive"))
      (node (ref "R88") (pin "1") (pintype "passive"))
      (node (ref "U16") (pin "9") (pinfunction "UVLO_Vsec_9") (pintype "passive"))
    )
    (net (code "35") (name "Net-(U17-A)") (class "Default")
      (node (ref "C108") (pin "2") (pintype "passive"))
      (node (ref "R91") (pin "1") (pintype "passive"))
      (node (ref "U17") (pin "1") (pinfunction "A_1") (pintype "passive"))
    )
    (net (code "36") (name "Net-(U17-C)") (class "Default")
      (node (ref "C104") (pin "1") (pintype "passive"))
      (node (ref "R97") (pin "1") (pintype "passive"))
      (node (ref "U17") (pin "4") (pinfunction "C_4") (pintype "passive"))
    )
    (net (code "37") (name "Net-(U17-E)") (class "Default")
      (node (ref "C103") (pin "1") (pintype "passive"))
      (node (ref "R94") (pin "1") (pintype "passive"))
      (node (ref "U17") (pin "3") (pinfunction "E_3") (pintype "passive"))
      (node (ref "U18") (pin "1") (pinfunction "COLL_1") (pintype "passive"))
    )
    (net (code "38") (name "Net-(U17-K)") (class "Default")
      (node (ref "R101") (pin "2") (pintype "passive"))
      (node (ref "R99") (pin "2") (pintype "passive"))
      (node (ref "U17") (pin "2") (pinfunction "K_2") (pintype "passive"))
    )
    (net (code "39") (name "Net-(U18-REF)") (class "Default")
      (node (ref "C103") (pin "2") (pintype "passive"))
      (node (ref "C106") (pin "2") (pintype "passive"))
      (node (ref "R102") (pin "2") (pintype "passive"))
      (node (ref "R95") (pin "1") (pintype "passive"))
      (node (ref "U18") (pin "8") (pinfunction "REF_8") (pintype "passive"))
    )
    (net (code "40") (name "unconnected-(U16-NC-Pad2)") (class "Default")
      (node (ref "U16") (pin "2") (pinfunction "NC_2") (pintype "passive+no_connect"))
    )
    (net (code "41") (name "unconnected-(U16-NC-Pad15)") (class "Default")
      (node (ref "U16") (pin "15") (pinfunction "NC_15") (pintype "passive+no_connect"))
    )
    (net (code "42") (name "unconnected-(U16-NC-Pad16)") (class "Default")
      (node (ref "U16") (pin "16") (pinfunction "NC_16") (pintype "passive+no_connect"))
    )
    (net (code "43") (name "unconnected-(U16-NC-Pad34)") (class "Default")
      (node (ref "U16") (pin "34") (pinfunction "NC_34") (pintype "passive+no_connect"))
    )
    (net (code "44") (name "unconnected-(U16-NC-Pad37)") (class "Default")
      (node (ref "U16") (pin "37") (pinfunction "NC_37") (pintype "passive+no_connect"))
    )
    (net (code "45") (name "unconnected-(U16-SOUT-Pad30)") (class "Default")
      (node (ref "U16") (pin "30") (pinfunction "SOUT_30") (pintype "passive+no_connect"))
    )
    (net (code "46") (name "unconnected-(U16-TEST1-Pad1)") (class "Default")
      (node (ref "U16") (pin "1") (pinfunction "TEST1_1") (pintype "passive+no_connect"))
    )
    (net (code "47") (name "unconnected-(U16-TEST2-Pad36)") (class "Default")
      (node (ref "U16") (pin "36") (pinfunction "TEST2_36") (pintype "passive+no_connect"))
    )
    (net (code "48") (name "unconnected-(U18-COMP-Pad2)") (class "Default")
      (node (ref "U18") (pin "2") (pinfunction "COMP_2") (pintype "passive+no_connect"))
    )
    (net (code "49") (name "unconnected-(U18-Rmid-Pad7)") (class "Default")
      (node (ref "U18") (pin "7") (pinfunction "Rmid_7") (pintype "passive+no_connect"))
    )
    (net (code "50") (name "unconnected-(U18-Rtop-Pad4)") (class "Default")
      (node (ref "U18") (pin "4") (pinfunction "Rtop_4") (pintype "passive+no_connect"))
    )
  )
)
